# device_board.net
KiCad netlist of a schematic drawn in EAGLE
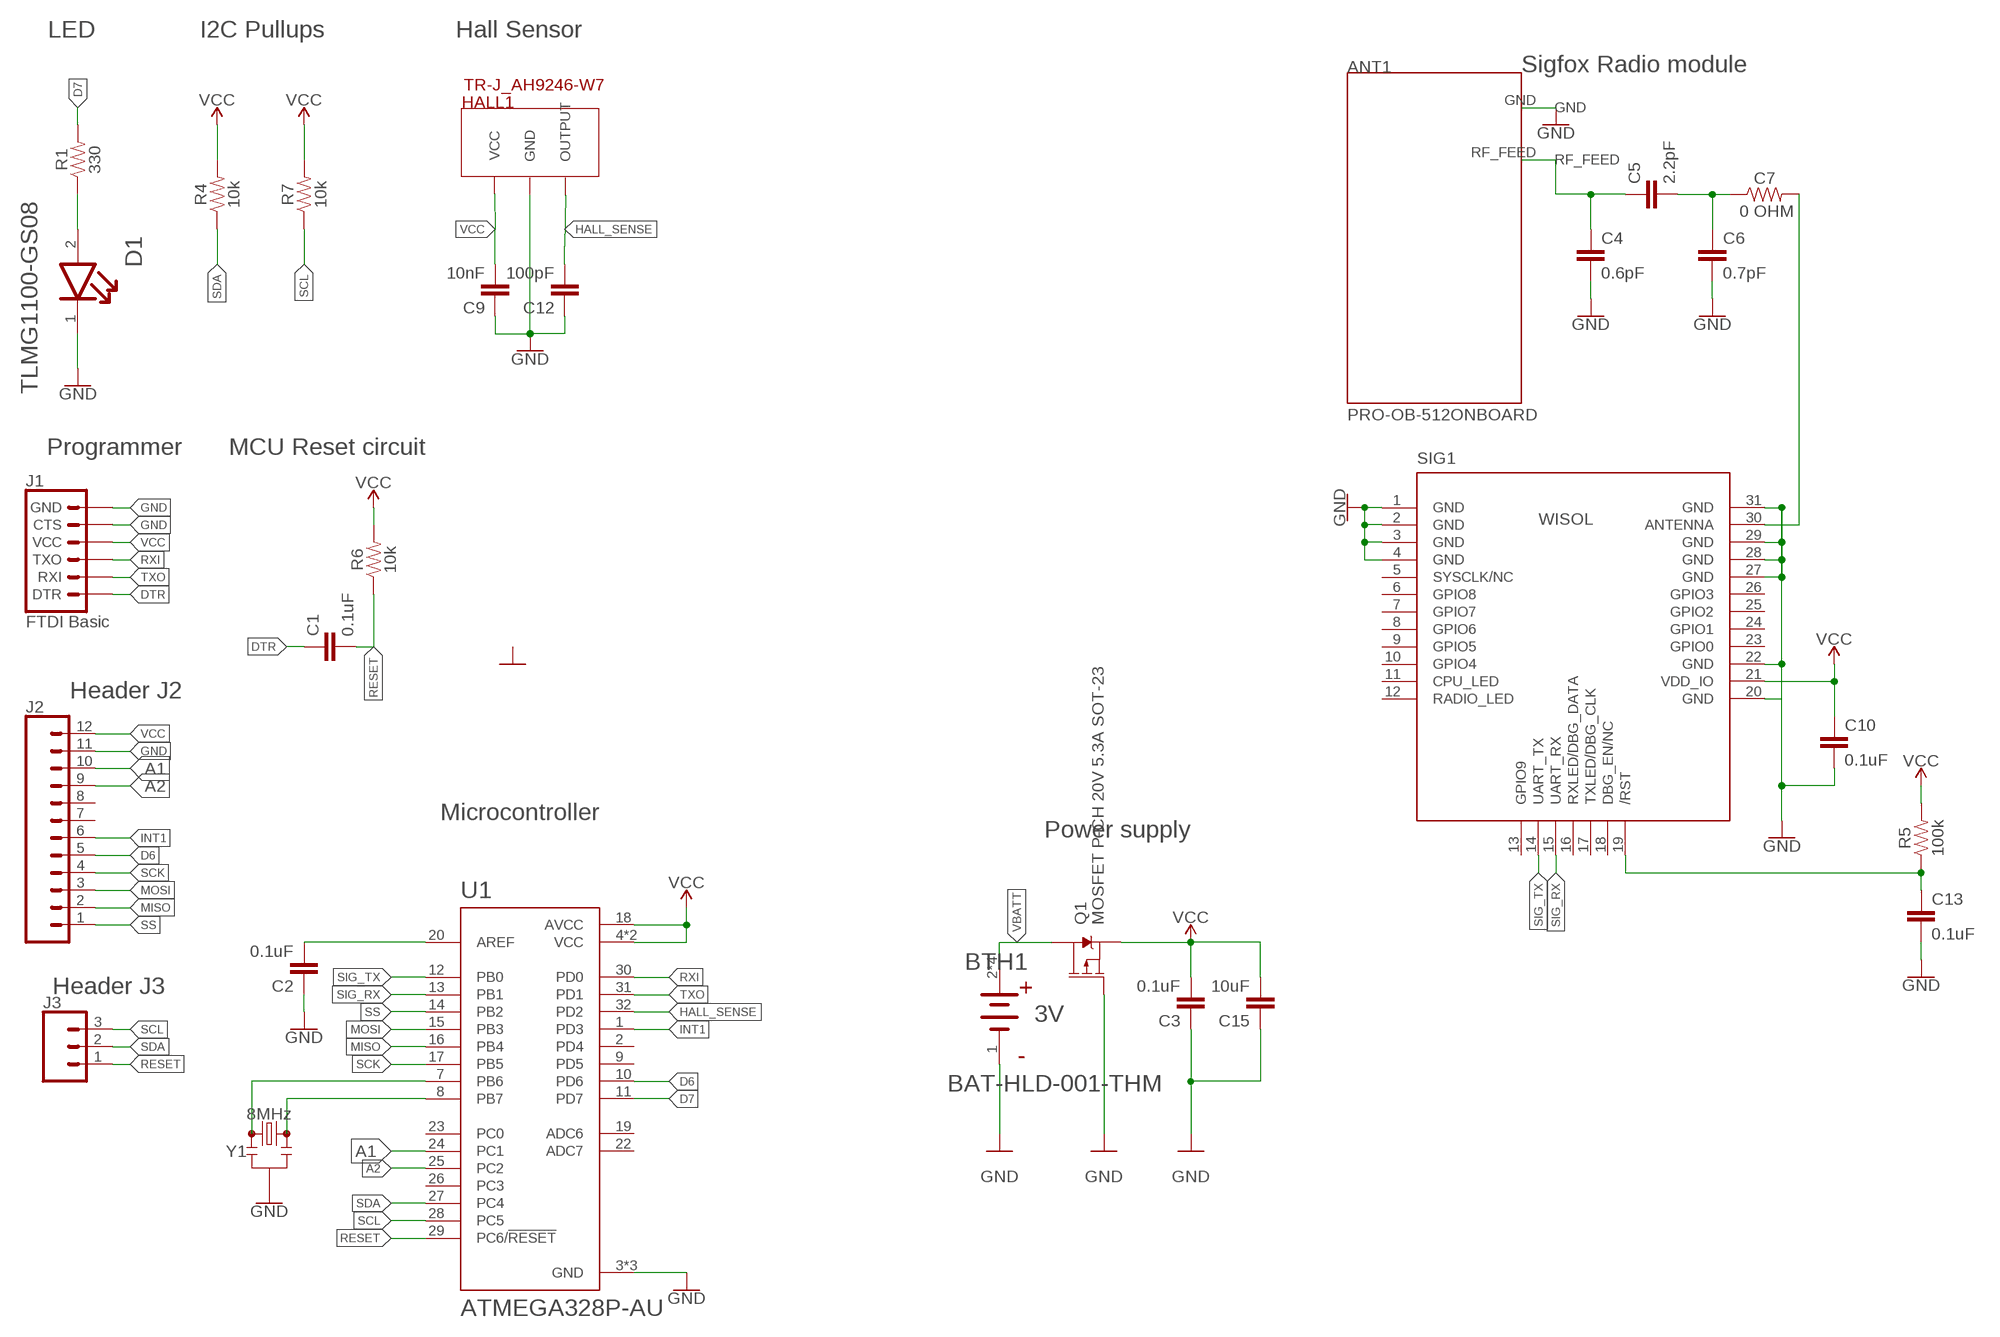
[diagram p0: schematic, sheet 1]

(export (version "E")
  (design (tool "Eeschema 10.0.6"))
  (components
    (comp (ref "ANT1")
      (value "PRO-OB-512ONBOARD")
      (footprint "eagle-import:ONBOARD_SMD_2400")
      (libsource (lib "eagle-import") (part "PRO-OB-512ONBOARD"))
    )
    (comp (ref "BTH1")
      (value "LINX_BAT-HLD-001-THMLINX_BAT-HLD-001-THM_0_0")
      (footprint "eagle-import:LINX_BAT-HLD-001-THM_0")
      (fields
        (field (name "DIGIKEY_PART_NUMBER") "BAT-HLD-001-THM-ND")
        (field (name "MF") "Linx")
        (field (name "MOUSER_PART_NUMBER") "712-BAT-HLD-001-THM")
      )
      (libsource (lib "eagle-import") (part "LINX_BAT-HLD-001-THMLINX_BAT-HLD-001-THM_0_0"))
    )
    (comp (ref "C1")
      (value "0.1uF")
      (footprint "eagle-import:0603")
      (libsource (lib "eagle-import") (part "0.1UF-0603-25V-5%"))
    )
    (comp (ref "C2")
      (value "0.1uF")
      (footprint "eagle-import:0603")
      (libsource (lib "eagle-import") (part "0.1UF-0603-25V-5%"))
    )
    (comp (ref "C3")
      (value "0.1uF")
      (footprint "eagle-import:0603")
      (libsource (lib "eagle-import") (part "0.1UF-0603-25V-5%"))
    )
    (comp (ref "C4")
      (value "0.6pF")
      (footprint "eagle-import:0402")
      (libsource (lib "eagle-import") (part "0.8PF-0402-50V-0.1PF"))
    )
    (comp (ref "C5")
      (value "2.2pF")
      (footprint "eagle-import:0402")
      (libsource (lib "eagle-import") (part "0.8PF-0402-50V-0.1PF"))
    )
    (comp (ref "C6")
      (value "0.7pF")
      (footprint "eagle-import:0402")
      (libsource (lib "eagle-import") (part "0.8PF-0402-50V-0.1PF"))
    )
    (comp (ref "C7")
      (value "0 OHM")
      (footprint "eagle-import:0402")
      (libsource (lib "eagle-import") (part "RESISTOR0402"))
    )
    (comp (ref "C9")
      (value "10nF")
      (footprint "eagle-import:0603")
      (libsource (lib "eagle-import") (part "10NF-0603-50V-10%"))
    )
    (comp (ref "C10")
      (value "0.1uF")
      (footprint "eagle-import:0603")
      (libsource (lib "eagle-import") (part "0.1UF-0603-25V-(+80/-20%)"))
    )
    (comp (ref "C12")
      (value "100pF")
      (footprint "eagle-import:0603")
      (libsource (lib "eagle-import") (part "100PF-0603-50V-5%"))
    )
    (comp (ref "C13")
      (value "0.1uF")
      (footprint "eagle-import:0603")
      (libsource (lib "eagle-import") (part "0.1UF-0603-25V-(+80/-20%)"))
    )
    (comp (ref "C15")
      (value "10uF")
      (footprint "eagle-import:0603")
      (libsource (lib "eagle-import") (part "10UF-0603-6.3V-20%"))
    )
    (comp (ref "D1")
      (value "VISHAY_TLMG1100-GS08VISHAY_TLMG1100-GS08_0_0")
      (footprint "eagle-import:VISHAY_TLMG1100-GS08_0")
      (fields
        (field (name "DIGIKEY_PART_NUMBER") "751-1165-1-ND")
        (field (name "MF") "Vishay")
        (field (name "MOUSER_PART_NUMBER") "78-TLMG1100")
      )
      (libsource (lib "eagle-import") (part "VISHAY_TLMG1100-GS08VISHAY_TLMG1100-GS08_0_0"))
    )
    (comp (ref "HALL1")
      (value "TR-J_AH9246-W7")
      (footprint "eagle-import:TR-J_SC-59")
      (libsource (lib "eagle-import") (part "TR-J_AH9246-W7"))
    )
    (comp (ref "J1")
      (value "FTDI Basic")
      (footprint "eagle-import:1X06")
      (libsource (lib "eagle-import") (part "6_PIN_SERIAL_TARGET"))
    )
    (comp (ref "J2")
      (value "CONN_12")
      (footprint "eagle-import:1X12")
      (libsource (lib "eagle-import") (part "CONN_12"))
    )
    (comp (ref "J3")
      (value "CONN_03")
      (footprint "eagle-import:1X03")
      (libsource (lib "eagle-import") (part "CONN_03"))
    )
    (comp (ref "Q1")
      (value "MOSFET P-CH 20V 5.3A SOT-23")
      (footprint "eagle-import:SOT23-3")
      (libsource (lib "eagle-import") (part "MOSFET_PCHSI2323DDS"))
    )
    (comp (ref "R1")
      (value "330")
      (footprint "eagle-import:0603")
      (libsource (lib "eagle-import") (part "330OHM-0603-1/10W-1%"))
    )
    (comp (ref "R4")
      (value "10k")
      (footprint "eagle-import:0603")
      (libsource (lib "eagle-import") (part "10KOHM-0603-1/10W-1%"))
    )
    (comp (ref "R5")
      (value "100k")
      (footprint "eagle-import:0603")
      (libsource (lib "eagle-import") (part "100KOHM-0603-1/10W-1%"))
    )
    (comp (ref "R6")
      (value "10k")
      (footprint "eagle-import:0603")
      (libsource (lib "eagle-import") (part "10KOHM-0603-1/10W-1%"))
    )
    (comp (ref "R7")
      (value "10k")
      (footprint "eagle-import:0603")
      (libsource (lib "eagle-import") (part "10KOHM-0603-1/10W-1%"))
    )
    (comp (ref "SIG1")
      (value "WISOL_WSSFM10HANDSOLDER")
      (footprint "eagle-import:WISOL_WSSFM10")
      (libsource (lib "eagle-import") (part "WISOL_WSSFM10HANDSOLDER"))
    )
    (comp (ref "U1")
      (value "ATMEGA328P-AU")
      (footprint "eagle-import:QFP80P900X900X120-32N")
      (fields (field (name "MF") "Microchip"))
      (libsource (lib "eagle-import") (part "ATMEGA328P-AU"))
    )
    (comp (ref "Y1")
      (value "8MHz")
      (footprint "eagle-import:RESONATOR-SMD-3.2X1.3")
      (libsource (lib "eagle-import") (part "RESONATOR-8MHZSMD_3.2X1.3"))
    )
  )
  (nets
    (net (code "1") (name "A1") (class "Default")
      (node (ref "J2") (pin "10") (pinfunction "10_10") (pintype "passive"))
      (node (ref "U1") (pin "24") (pinfunction "PC1_24") (pintype "bidirectional"))
    )
    (net (code "2") (name "A2") (class "Default")
      (node (ref "J2") (pin "9") (pinfunction "9_9") (pintype "passive"))
      (node (ref "U1") (pin "25") (pinfunction "PC2_25") (pintype "bidirectional"))
    )
    (net (code "3") (name "D6") (class "Default")
      (node (ref "J2") (pin "5") (pinfunction "5_5") (pintype "passive"))
      (node (ref "U1") (pin "10") (pinfunction "PD6_10") (pintype "bidirectional"))
    )
    (net (code "4") (name "D7") (class "Default")
      (node (ref "R1") (pin "2") (pinfunction "2_2") (pintype "passive"))
      (node (ref "U1") (pin "11") (pinfunction "PD7_11") (pintype "bidirectional"))
    )
    (net (code "5") (name "DTR") (class "Default")
      (node (ref "C1") (pin "1") (pinfunction "1_1") (pintype "passive"))
      (node (ref "J1") (pin "1") (pinfunction "DTR_1") (pintype "passive"))
    )
    (net (code "6") (name "GND") (class "Default")
      (node (ref "ANT1") (pin "GND") (pinfunction "GND_GND") (pintype "power_in"))
      (node (ref "BTH1") (pin "1") (pinfunction "CATHODE_1") (pintype "bidirectional"))
      (node (ref "C10") (pin "2") (pinfunction "2_2") (pintype "passive"))
      (node (ref "C12") (pin "1") (pinfunction "1_1") (pintype "passive"))
      (node (ref "C13") (pin "2") (pinfunction "2_2") (pintype "passive"))
      (node (ref "C15") (pin "1") (pinfunction "1_1") (pintype "passive"))
      (node (ref "C2") (pin "1") (pinfunction "1_1") (pintype "passive"))
      (node (ref "C3") (pin "1") (pinfunction "1_1") (pintype "passive"))
      (node (ref "C4") (pin "2") (pinfunction "2_2") (pintype "passive"))
      (node (ref "C6") (pin "2") (pinfunction "2_2") (pintype "passive"))
      (node (ref "C9") (pin "1") (pinfunction "1_1") (pintype "passive"))
      (node (ref "D1") (pin "1") (pinfunction "CATHODE_1") (pintype "passive"))
      (node (ref "HALL1") (pin "3") (pinfunction "GND_3") (pintype "power_in"))
      (node (ref "J1") (pin "5") (pinfunction "CTS_5") (pintype "passive"))
      (node (ref "J1") (pin "6") (pinfunction "GND_6") (pintype "passive"))
      (node (ref "J2") (pin "11") (pinfunction "11_11") (pintype "passive"))
      (node (ref "Q1") (pin "1") (pinfunction "G_1") (pintype "bidirectional"))
      (node (ref "SIG1") (pin "1") (pinfunction "GND_1") (pintype "power_in"))
      (node (ref "SIG1") (pin "2") (pinfunction "GND_2") (pintype "power_in"))
      (node (ref "SIG1") (pin "20") (pinfunction "GND_20") (pintype "power_in"))
      (node (ref "SIG1") (pin "22") (pinfunction "GND_22") (pintype "power_in"))
      (node (ref "SIG1") (pin "27") (pinfunction "GND_27") (pintype "power_in"))
      (node (ref "SIG1") (pin "28") (pinfunction "GND_28") (pintype "power_in"))
      (node (ref "SIG1") (pin "29") (pinfunction "GND_29") (pintype "power_in"))
      (node (ref "SIG1") (pin "3") (pinfunction "GND_3") (pintype "power_in"))
      (node (ref "SIG1") (pin "31") (pinfunction "GND_31") (pintype "power_in"))
      (node (ref "SIG1") (pin "4") (pinfunction "GND_4") (pintype "power_in"))
      (node (ref "U1") (pin "21") (pinfunction "GND_21") (pintype "power_in"))
      (node (ref "U1") (pin "3") (pinfunction "GND_3") (pintype "power_in"))
      (node (ref "U1") (pin "5") (pinfunction "GND_5") (pintype "power_in"))
      (node (ref "Y1") (pin "2") (pinfunction "2_2") (pintype "passive"))
    )
    (net (code "7") (name "HALL_SENSE") (class "Default")
      (node (ref "C12") (pin "2") (pinfunction "2_2") (pintype "passive"))
      (node (ref "HALL1") (pin "2") (pinfunction "OUTPUT_2") (pintype "output"))
      (node (ref "U1") (pin "32") (pinfunction "PD2_32") (pintype "bidirectional"))
    )
    (net (code "8") (name "INT1") (class "Default")
      (node (ref "J2") (pin "6") (pinfunction "6_6") (pintype "passive"))
      (node (ref "U1") (pin "1") (pinfunction "PD3_1") (pintype "bidirectional"))
    )
    (net (code "9") (name "MISO") (class "Default")
      (node (ref "J2") (pin "2") (pinfunction "2_2") (pintype "passive"))
      (node (ref "U1") (pin "16") (pinfunction "PB4_16") (pintype "bidirectional"))
    )
    (net (code "10") (name "MOSI") (class "Default")
      (node (ref "J2") (pin "3") (pinfunction "3_3") (pintype "passive"))
      (node (ref "U1") (pin "15") (pinfunction "PB3_15") (pintype "bidirectional"))
    )
    (net (code "11") (name "Net-(ANT1-PadRF_FEED)") (class "Default")
      (node (ref "ANT1") (pin "RF_FEED") (pinfunction "RF_FEED_RF_FEED") (pintype "input"))
      (node (ref "C4") (pin "1") (pinfunction "1_1") (pintype "passive"))
      (node (ref "C5") (pin "1") (pinfunction "1_1") (pintype "passive"))
    )
    (net (code "12") (name "Net-(C5-Pad2)") (class "Default")
      (node (ref "C5") (pin "2") (pinfunction "2_2") (pintype "passive"))
      (node (ref "C6") (pin "1") (pinfunction "1_1") (pintype "passive"))
      (node (ref "C7") (pin "1") (pinfunction "1_1") (pintype "passive"))
    )
    (net (code "13") (name "Net-(D1-ANODE)") (class "Default")
      (node (ref "D1") (pin "2") (pinfunction "ANODE_2") (pintype "passive"))
      (node (ref "R1") (pin "1") (pinfunction "1_1") (pintype "passive"))
    )
    (net (code "14") (name "Net-(SIG1-ANTENNA)") (class "Default")
      (node (ref "C7") (pin "2") (pinfunction "2_2") (pintype "passive"))
      (node (ref "SIG1") (pin "30") (pinfunction "ANTENNA_30") (pintype "output"))
    )
    (net (code "15") (name "Net-(SIG1-{slash}RST)") (class "Default")
      (node (ref "C13") (pin "1") (pinfunction "1_1") (pintype "passive"))
      (node (ref "R5") (pin "1") (pinfunction "1_1") (pintype "passive"))
      (node (ref "SIG1") (pin "19") (pinfunction "/RST_19") (pintype "input"))
    )
    (net (code "16") (name "Net-(U1-AREF)") (class "Default")
      (node (ref "C2") (pin "2") (pinfunction "2_2") (pintype "passive"))
      (node (ref "U1") (pin "20") (pinfunction "AREF_20") (pintype "input"))
    )
    (net (code "17") (name "Net-(U1-PB6)") (class "Default")
      (node (ref "U1") (pin "7") (pinfunction "PB6_7") (pintype "bidirectional"))
      (node (ref "Y1") (pin "1") (pinfunction "1_1") (pintype "passive"))
    )
    (net (code "18") (name "Net-(U1-PB7)") (class "Default")
      (node (ref "U1") (pin "8") (pinfunction "PB7_8") (pintype "bidirectional"))
      (node (ref "Y1") (pin "3") (pinfunction "3_3") (pintype "passive"))
    )
    (net (code "19") (name "RESET") (class "Default")
      (node (ref "C1") (pin "2") (pinfunction "2_2") (pintype "passive"))
      (node (ref "J3") (pin "1") (pinfunction "1_1") (pintype "passive"))
      (node (ref "R6") (pin "1") (pinfunction "1_1") (pintype "passive"))
      (node (ref "U1") (pin "29") (pinfunction "PC6/~{RESET}_29") (pintype "bidirectional"))
    )
    (net (code "20") (name "RXI") (class "Default")
      (node (ref "J1") (pin "3") (pinfunction "TXO_3") (pintype "passive"))
      (node (ref "U1") (pin "30") (pinfunction "PD0_30") (pintype "bidirectional"))
    )
    (net (code "21") (name "SCK") (class "Default")
      (node (ref "J2") (pin "4") (pinfunction "4_4") (pintype "passive"))
      (node (ref "U1") (pin "17") (pinfunction "PB5_17") (pintype "bidirectional"))
    )
    (net (code "22") (name "SCL") (class "Default")
      (node (ref "J3") (pin "3") (pinfunction "3_3") (pintype "passive"))
      (node (ref "R7") (pin "1") (pinfunction "1_1") (pintype "passive"))
      (node (ref "U1") (pin "28") (pinfunction "PC5_28") (pintype "bidirectional"))
    )
    (net (code "23") (name "SDA") (class "Default")
      (node (ref "J3") (pin "2") (pinfunction "2_2") (pintype "passive"))
      (node (ref "R4") (pin "1") (pinfunction "1_1") (pintype "passive"))
      (node (ref "U1") (pin "27") (pinfunction "PC4_27") (pintype "bidirectional"))
    )
    (net (code "24") (name "SIG_RX") (class "Default")
      (node (ref "SIG1") (pin "15") (pinfunction "UART_RX_15") (pintype "input"))
      (node (ref "U1") (pin "13") (pinfunction "PB1_13") (pintype "bidirectional"))
    )
    (net (code "25") (name "SIG_TX") (class "Default")
      (node (ref "SIG1") (pin "14") (pinfunction "UART_TX_14") (pintype "output"))
      (node (ref "U1") (pin "12") (pinfunction "PB0_12") (pintype "bidirectional"))
    )
    (net (code "26") (name "SS") (class "Default")
      (node (ref "J2") (pin "1") (pinfunction "1_1") (pintype "passive"))
      (node (ref "U1") (pin "14") (pinfunction "PB2_14") (pintype "bidirectional"))
    )
    (net (code "27") (name "TXO") (class "Default")
      (node (ref "J1") (pin "2") (pinfunction "RXI_2") (pintype "passive"))
      (node (ref "U1") (pin "31") (pinfunction "PD1_31") (pintype "bidirectional"))
    )
    (net (code "28") (name "VBATT") (class "Default")
      (node (ref "BTH1") (pin "2") (pinfunction "ANODE_2") (pintype "bidirectional"))
      (node (ref "BTH1") (pin "2-2") (pinfunction "ANODE_2-2") (pintype "bidirectional"))
      (node (ref "BTH1") (pin "2-3") (pinfunction "ANODE_2-3") (pintype "bidirectional"))
      (node (ref "BTH1") (pin "2-4") (pinfunction "ANODE_2-4") (pintype "bidirectional"))
      (node (ref "Q1") (pin "3") (pinfunction "D_3") (pintype "bidirectional"))
    )
    (net (code "29") (name "VCC") (class "Default")
      (node (ref "C10") (pin "1") (pinfunction "1_1") (pintype "passive"))
      (node (ref "C15") (pin "2") (pinfunction "2_2") (pintype "passive"))
      (node (ref "C3") (pin "2") (pinfunction "2_2") (pintype "passive"))
      (node (ref "C9") (pin "2") (pinfunction "2_2") (pintype "passive"))
      (node (ref "HALL1") (pin "1") (pinfunction "VCC_1") (pintype "power_in"))
      (node (ref "J1") (pin "4") (pinfunction "VCC_4") (pintype "passive"))
      (node (ref "J2") (pin "12") (pinfunction "12_12") (pintype "passive"))
      (node (ref "Q1") (pin "2") (pinfunction "S_2") (pintype "bidirectional"))
      (node (ref "R4") (pin "2") (pinfunction "2_2") (pintype "passive"))
      (node (ref "R5") (pin "2") (pinfunction "2_2") (pintype "passive"))
      (node (ref "R6") (pin "2") (pinfunction "2_2") (pintype "passive"))
      (node (ref "R7") (pin "2") (pinfunction "2_2") (pintype "passive"))
      (node (ref "SIG1") (pin "21") (pinfunction "VDD_IO_21") (pintype "power_in"))
      (node (ref "U1") (pin "18") (pinfunction "AVCC_18") (pintype "power_in"))
      (node (ref "U1") (pin "4") (pinfunction "VCC_4") (pintype "power_in"))
      (node (ref "U1") (pin "6") (pinfunction "VCC_6") (pintype "power_in"))
    )
    (net (code "30") (name "unconnected-(J2-Pad7)") (class "Default")
      (node (ref "J2") (pin "7") (pinfunction "7_7") (pintype "passive"))
    )
    (net (code "31") (name "unconnected-(J2-Pad8)") (class "Default")
      (node (ref "J2") (pin "8") (pinfunction "8_8") (pintype "passive"))
    )
    (net (code "32") (name "unconnected-(SIG1-CPU_LED-Pad11)") (class "Default")
      (node (ref "SIG1") (pin "11") (pinfunction "CPU_LED_11") (pintype "output"))
    )
    (net (code "33") (name "unconnected-(SIG1-DBG_EN{slash}NC-Pad18)") (class "Default")
      (node (ref "SIG1") (pin "18") (pinfunction "DBG_EN/NC_18") (pintype "no_connect"))
    )
    (net (code "34") (name "unconnected-(SIG1-GPIO0-Pad23)") (class "Default")
      (node (ref "SIG1") (pin "23") (pinfunction "GPIO0_23") (pintype "bidirectional"))
    )
    (net (code "35") (name "unconnected-(SIG1-GPIO1-Pad24)") (class "Default")
      (node (ref "SIG1") (pin "24") (pinfunction "GPIO1_24") (pintype "bidirectional"))
    )
    (net (code "36") (name "unconnected-(SIG1-GPIO2-Pad25)") (class "Default")
      (node (ref "SIG1") (pin "25") (pinfunction "GPIO2_25") (pintype "bidirectional"))
    )
    (net (code "37") (name "unconnected-(SIG1-GPIO3-Pad26)") (class "Default")
      (node (ref "SIG1") (pin "26") (pinfunction "GPIO3_26") (pintype "bidirectional"))
    )
    (net (code "38") (name "unconnected-(SIG1-GPIO4-Pad10)") (class "Default")
      (node (ref "SIG1") (pin "10") (pinfunction "GPIO4_10") (pintype "bidirectional"))
    )
    (net (code "39") (name "unconnected-(SIG1-GPIO5-Pad9)") (class "Default")
      (node (ref "SIG1") (pin "9") (pinfunction "GPIO5_9") (pintype "bidirectional"))
    )
    (net (code "40") (name "unconnected-(SIG1-GPIO6-Pad8)") (class "Default")
      (node (ref "SIG1") (pin "8") (pinfunction "GPIO6_8") (pintype "bidirectional"))
    )
    (net (code "41") (name "unconnected-(SIG1-GPIO7-Pad7)") (class "Default")
      (node (ref "SIG1") (pin "7") (pinfunction "GPIO7_7") (pintype "bidirectional"))
    )
    (net (code "42") (name "unconnected-(SIG1-GPIO8-Pad6)") (class "Default")
      (node (ref "SIG1") (pin "6") (pinfunction "GPIO8_6") (pintype "bidirectional"))
    )
    (net (code "43") (name "unconnected-(SIG1-GPIO9-Pad13)") (class "Default")
      (node (ref "SIG1") (pin "13") (pinfunction "GPIO9_13") (pintype "bidirectional"))
    )
    (net (code "44") (name "unconnected-(SIG1-RADIO_LED-Pad12)") (class "Default")
      (node (ref "SIG1") (pin "12") (pinfunction "RADIO_LED_12") (pintype "output"))
    )
    (net (code "45") (name "unconnected-(SIG1-RXLED{slash}DBG_DATA-Pad16)") (class "Default")
      (node (ref "SIG1") (pin "16") (pinfunction "RXLED/DBG_DATA_16") (pintype "output"))
    )
    (net (code "46") (name "unconnected-(SIG1-SYSCLK{slash}NC-Pad5)") (class "Default")
      (node (ref "SIG1") (pin "5") (pinfunction "SYSCLK/NC_5") (pintype "no_connect"))
    )
    (net (code "47") (name "unconnected-(SIG1-TXLED{slash}DBG_CLK-Pad17)") (class "Default")
      (node (ref "SIG1") (pin "17") (pinfunction "TXLED/DBG_CLK_17") (pintype "output"))
    )
    (net (code "48") (name "unconnected-(U1-ADC6-Pad19)") (class "Default")
      (node (ref "U1") (pin "19") (pinfunction "ADC6_19") (pintype "bidirectional"))
    )
    (net (code "49") (name "unconnected-(U1-ADC7-Pad22)") (class "Default")
      (node (ref "U1") (pin "22") (pinfunction "ADC7_22") (pintype "bidirectional"))
    )
    (net (code "50") (name "unconnected-(U1-PC0-Pad23)") (class "Default")
      (node (ref "U1") (pin "23") (pinfunction "PC0_23") (pintype "bidirectional"))
    )
    (net (code "51") (name "unconnected-(U1-PC3-Pad26)") (class "Default")
      (node (ref "U1") (pin "26") (pinfunction "PC3_26") (pintype "bidirectional"))
    )
    (net (code "52") (name "unconnected-(U1-PD4-Pad2)") (class "Default")
      (node (ref "U1") (pin "2") (pinfunction "PD4_2") (pintype "bidirectional"))
    )
    (net (code "53") (name "unconnected-(U1-PD5-Pad9)") (class "Default")
      (node (ref "U1") (pin "9") (pinfunction "PD5_9") (pintype "bidirectional"))
    )
  )
)
